# blink1mk3_005t.net
KiCad netlist of a schematic drawn in EAGLE
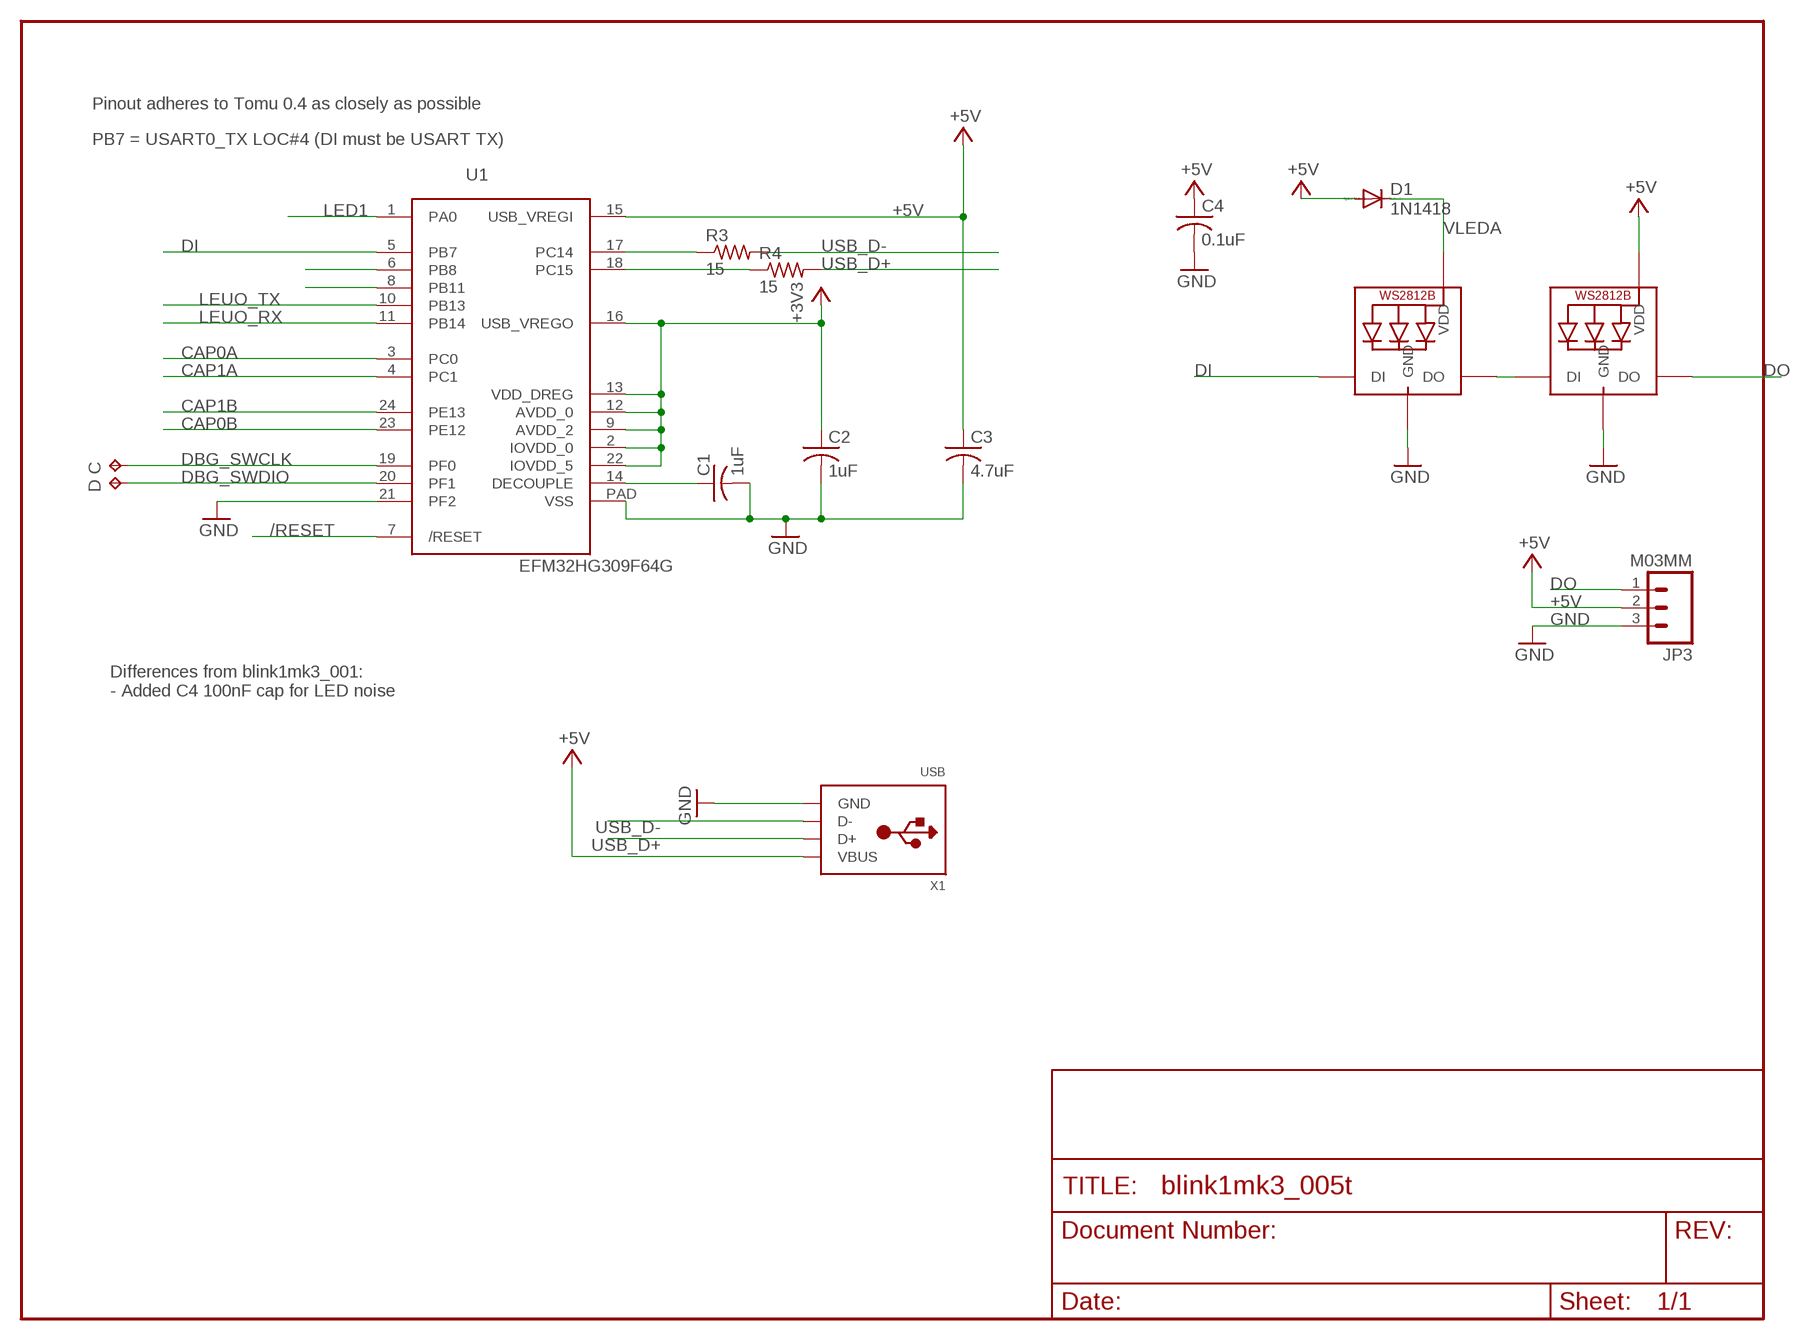
[diagram p0: schematic, sheet 1]

(export (version "E")
  (design (tool "Eeschema 10.0.6"))
  (components
    (comp (ref "C")
      (value "TPTP10R")
      (footprint "eagle-import:TP10R")
      (libsource (lib "eagle-import") (part "TPTP10R"))
    )
    (comp (ref "C1")
      (value "1uF")
      (footprint "eagle-import:C0402")
      (libsource (lib "eagle-import") (part "C-USC0402"))
    )
    (comp (ref "C2")
      (value "1uF")
      (footprint "eagle-import:C0402")
      (libsource (lib "eagle-import") (part "C-USC0402"))
    )
    (comp (ref "C3")
      (value "4.7uF")
      (footprint "eagle-import:C0402")
      (libsource (lib "eagle-import") (part "C-USC0402"))
    )
    (comp (ref "C4")
      (value "0.1uF")
      (footprint "eagle-import:C0402")
      (libsource (lib "eagle-import") (part "C-USC0402"))
    )
    (comp (ref "D")
      (value "TPTP10R")
      (footprint "eagle-import:TP10R")
      (libsource (lib "eagle-import") (part "TPTP10R"))
    )
    (comp (ref "D1")
      (value "1N1418")
      (footprint "eagle-import:SOD523")
      (libsource (lib "eagle-import") (part "DIODE-SOD523"))
    )
    (comp (ref "JP3")
      (value "M03MM")
      (footprint "eagle-import:1X03-1.5MM")
      (libsource (lib "eagle-import") (part "M03MM"))
    )
    (comp (ref "LED1")
      (value "SK6812MINI")
      (footprint "eagle-import:LED3535")
      (libsource (lib "eagle-import") (part "WS2812B3535"))
    )
    (comp (ref "LED2")
      (value "SK6812MINI")
      (footprint "eagle-import:LED3535")
      (libsource (lib "eagle-import") (part "WS2812B3535"))
    )
    (comp (ref "R3")
      (value "15")
      (footprint "eagle-import:R0402")
      (libsource (lib "eagle-import") (part "R-US_R0402"))
    )
    (comp (ref "R4")
      (value "15")
      (footprint "eagle-import:R0402")
      (libsource (lib "eagle-import") (part "R-US_R0402"))
    )
    (comp (ref "U1")
      (value "EFM32HG309F64G")
      (footprint "eagle-import:QFN24PAD")
      (libsource (lib "eagle-import") (part "EFM32HG309F64G"))
    )
    (comp (ref "X1")
      (value "USB")
      (footprint "eagle-import:MOLEX-48037-1000")
      (libsource (lib "eagle-import") (part "USB"))
    )
  )
  (nets
    (net (code "1") (name "+3V3") (class "Default")
      (node (ref "C2") (pin "1") (pinfunction "1_1") (pintype "passive"))
      (node (ref "U1") (pin "12") (pinfunction "AVDD_0_12") (pintype "bidirectional"))
      (node (ref "U1") (pin "13") (pinfunction "VDD_DREG_13") (pintype "bidirectional"))
      (node (ref "U1") (pin "16") (pinfunction "USB_VREGO_16") (pintype "bidirectional"))
      (node (ref "U1") (pin "2") (pinfunction "IOVDD_0_2") (pintype "bidirectional"))
      (node (ref "U1") (pin "22") (pinfunction "IOVDD_5_22") (pintype "bidirectional"))
      (node (ref "U1") (pin "9") (pinfunction "AVDD_2_9") (pintype "bidirectional"))
    )
    (net (code "2") (name "+5V") (class "Default")
      (node (ref "C3") (pin "1") (pinfunction "1_1") (pintype "passive"))
      (node (ref "C4") (pin "1") (pinfunction "1_1") (pintype "passive"))
      (node (ref "D1") (pin "A") (pinfunction "A_A") (pintype "passive"))
      (node (ref "JP3") (pin "2") (pinfunction "2_2") (pintype "passive"))
      (node (ref "LED2") (pin "2") (pinfunction "VDD_2") (pintype "power_in"))
      (node (ref "U1") (pin "15") (pinfunction "USB_VREGI_15") (pintype "bidirectional"))
      (node (ref "X1") (pin "1") (pinfunction "VBUS_1") (pintype "power_in"))
    )
    (net (code "3") (name "/CAP0A") (class "Default")
      (node (ref "U1") (pin "3") (pinfunction "PC0_3") (pintype "bidirectional"))
    )
    (net (code "4") (name "/CAP0B") (class "Default")
      (node (ref "U1") (pin "23") (pinfunction "PE12_23") (pintype "bidirectional"))
    )
    (net (code "5") (name "/CAP1A") (class "Default")
      (node (ref "U1") (pin "4") (pinfunction "PC1_4") (pintype "bidirectional"))
    )
    (net (code "6") (name "/CAP1B") (class "Default")
      (node (ref "U1") (pin "24") (pinfunction "PE13_24") (pintype "bidirectional"))
    )
    (net (code "7") (name "/DBG_SWCLK") (class "Default")
      (node (ref "C") (pin "TP") (pinfunction "TP_TP") (pintype "input"))
      (node (ref "U1") (pin "19") (pinfunction "PF0_19") (pintype "bidirectional"))
    )
    (net (code "8") (name "/DBG_SWDIO") (class "Default")
      (node (ref "D") (pin "TP") (pinfunction "TP_TP") (pintype "input"))
      (node (ref "U1") (pin "20") (pinfunction "PF1_20") (pintype "bidirectional"))
    )
    (net (code "9") (name "/DI") (class "Default")
      (node (ref "LED1") (pin "1") (pinfunction "DI_1") (pintype "input"))
      (node (ref "U1") (pin "5") (pinfunction "PB7_5") (pintype "bidirectional"))
    )
    (net (code "10") (name "/DO") (class "Default")
      (node (ref "JP3") (pin "1") (pinfunction "1_1") (pintype "passive"))
      (node (ref "LED2") (pin "3") (pinfunction "DO_3") (pintype "output"))
    )
    (net (code "11") (name "/LED1") (class "Default")
      (node (ref "U1") (pin "1") (pinfunction "PA0_1") (pintype "bidirectional"))
    )
    (net (code "12") (name "/LEUO_RX") (class "Default")
      (node (ref "U1") (pin "11") (pinfunction "PB14_11") (pintype "bidirectional"))
    )
    (net (code "13") (name "/LEUO_TX") (class "Default")
      (node (ref "U1") (pin "10") (pinfunction "PB13_10") (pintype "bidirectional"))
    )
    (net (code "14") (name "/USB_D+") (class "Default")
      (node (ref "R4") (pin "2") (pinfunction "2_2") (pintype "passive"))
      (node (ref "X1") (pin "3") (pinfunction "D+_3") (pintype "bidirectional"))
    )
    (net (code "15") (name "/USB_D-") (class "Default")
      (node (ref "R3") (pin "2") (pinfunction "2_2") (pintype "passive"))
      (node (ref "X1") (pin "2") (pinfunction "D-_2") (pintype "bidirectional"))
    )
    (net (code "16") (name "/VLEDA") (class "Default")
      (node (ref "D1") (pin "C") (pinfunction "C_C") (pintype "passive"))
      (node (ref "LED1") (pin "2") (pinfunction "VDD_2") (pintype "power_in"))
    )
    (net (code "17") (name "/{slash}RESET") (class "Default")
      (node (ref "U1") (pin "7") (pinfunction "/RESET_7") (pintype "bidirectional"))
    )
    (net (code "18") (name "GND") (class "Default")
      (node (ref "C1") (pin "2") (pinfunction "2_2") (pintype "passive"))
      (node (ref "C2") (pin "2") (pinfunction "2_2") (pintype "passive"))
      (node (ref "C3") (pin "2") (pinfunction "2_2") (pintype "passive"))
      (node (ref "C4") (pin "2") (pinfunction "2_2") (pintype "passive"))
      (node (ref "JP3") (pin "3") (pinfunction "3_3") (pintype "passive"))
      (node (ref "LED1") (pin "4") (pinfunction "GND_4") (pintype "power_in"))
      (node (ref "LED2") (pin "4") (pinfunction "GND_4") (pintype "power_in"))
      (node (ref "U1") (pin "21") (pinfunction "PF2_21") (pintype "bidirectional"))
      (node (ref "U1") (pin "PAD") (pinfunction "VSS_PAD") (pintype "bidirectional"))
      (node (ref "X1") (pin "4") (pinfunction "GND_4") (pintype "power_in"))
    )
    (net (code "19") (name "Net-(LED1-DO)") (class "Default")
      (node (ref "LED1") (pin "3") (pinfunction "DO_3") (pintype "output"))
      (node (ref "LED2") (pin "1") (pinfunction "DI_1") (pintype "input"))
    )
    (net (code "20") (name "Net-(U1-DECOUPLE)") (class "Default")
      (node (ref "C1") (pin "1") (pinfunction "1_1") (pintype "passive"))
      (node (ref "U1") (pin "14") (pinfunction "DECOUPLE_14") (pintype "bidirectional"))
    )
    (net (code "21") (name "Net-(U1-PC14)") (class "Default")
      (node (ref "R3") (pin "1") (pinfunction "1_1") (pintype "passive"))
      (node (ref "U1") (pin "17") (pinfunction "PC14_17") (pintype "bidirectional"))
    )
    (net (code "22") (name "Net-(U1-PC15)") (class "Default")
      (node (ref "R4") (pin "1") (pinfunction "1_1") (pintype "passive"))
      (node (ref "U1") (pin "18") (pinfunction "PC15_18") (pintype "bidirectional"))
    )
    (net (code "23") (name "unconnected-(U1-PB8-Pad6)") (class "Default")
      (node (ref "U1") (pin "6") (pinfunction "PB8_6") (pintype "bidirectional"))
    )
    (net (code "24") (name "unconnected-(U1-PB11-Pad8)") (class "Default")
      (node (ref "U1") (pin "8") (pinfunction "PB11_8") (pintype "bidirectional"))
    )
  )
)
